# 1-Schematic_ecg_biometrics.net
KiCad netlist of a schematic drawn in EasyEDA
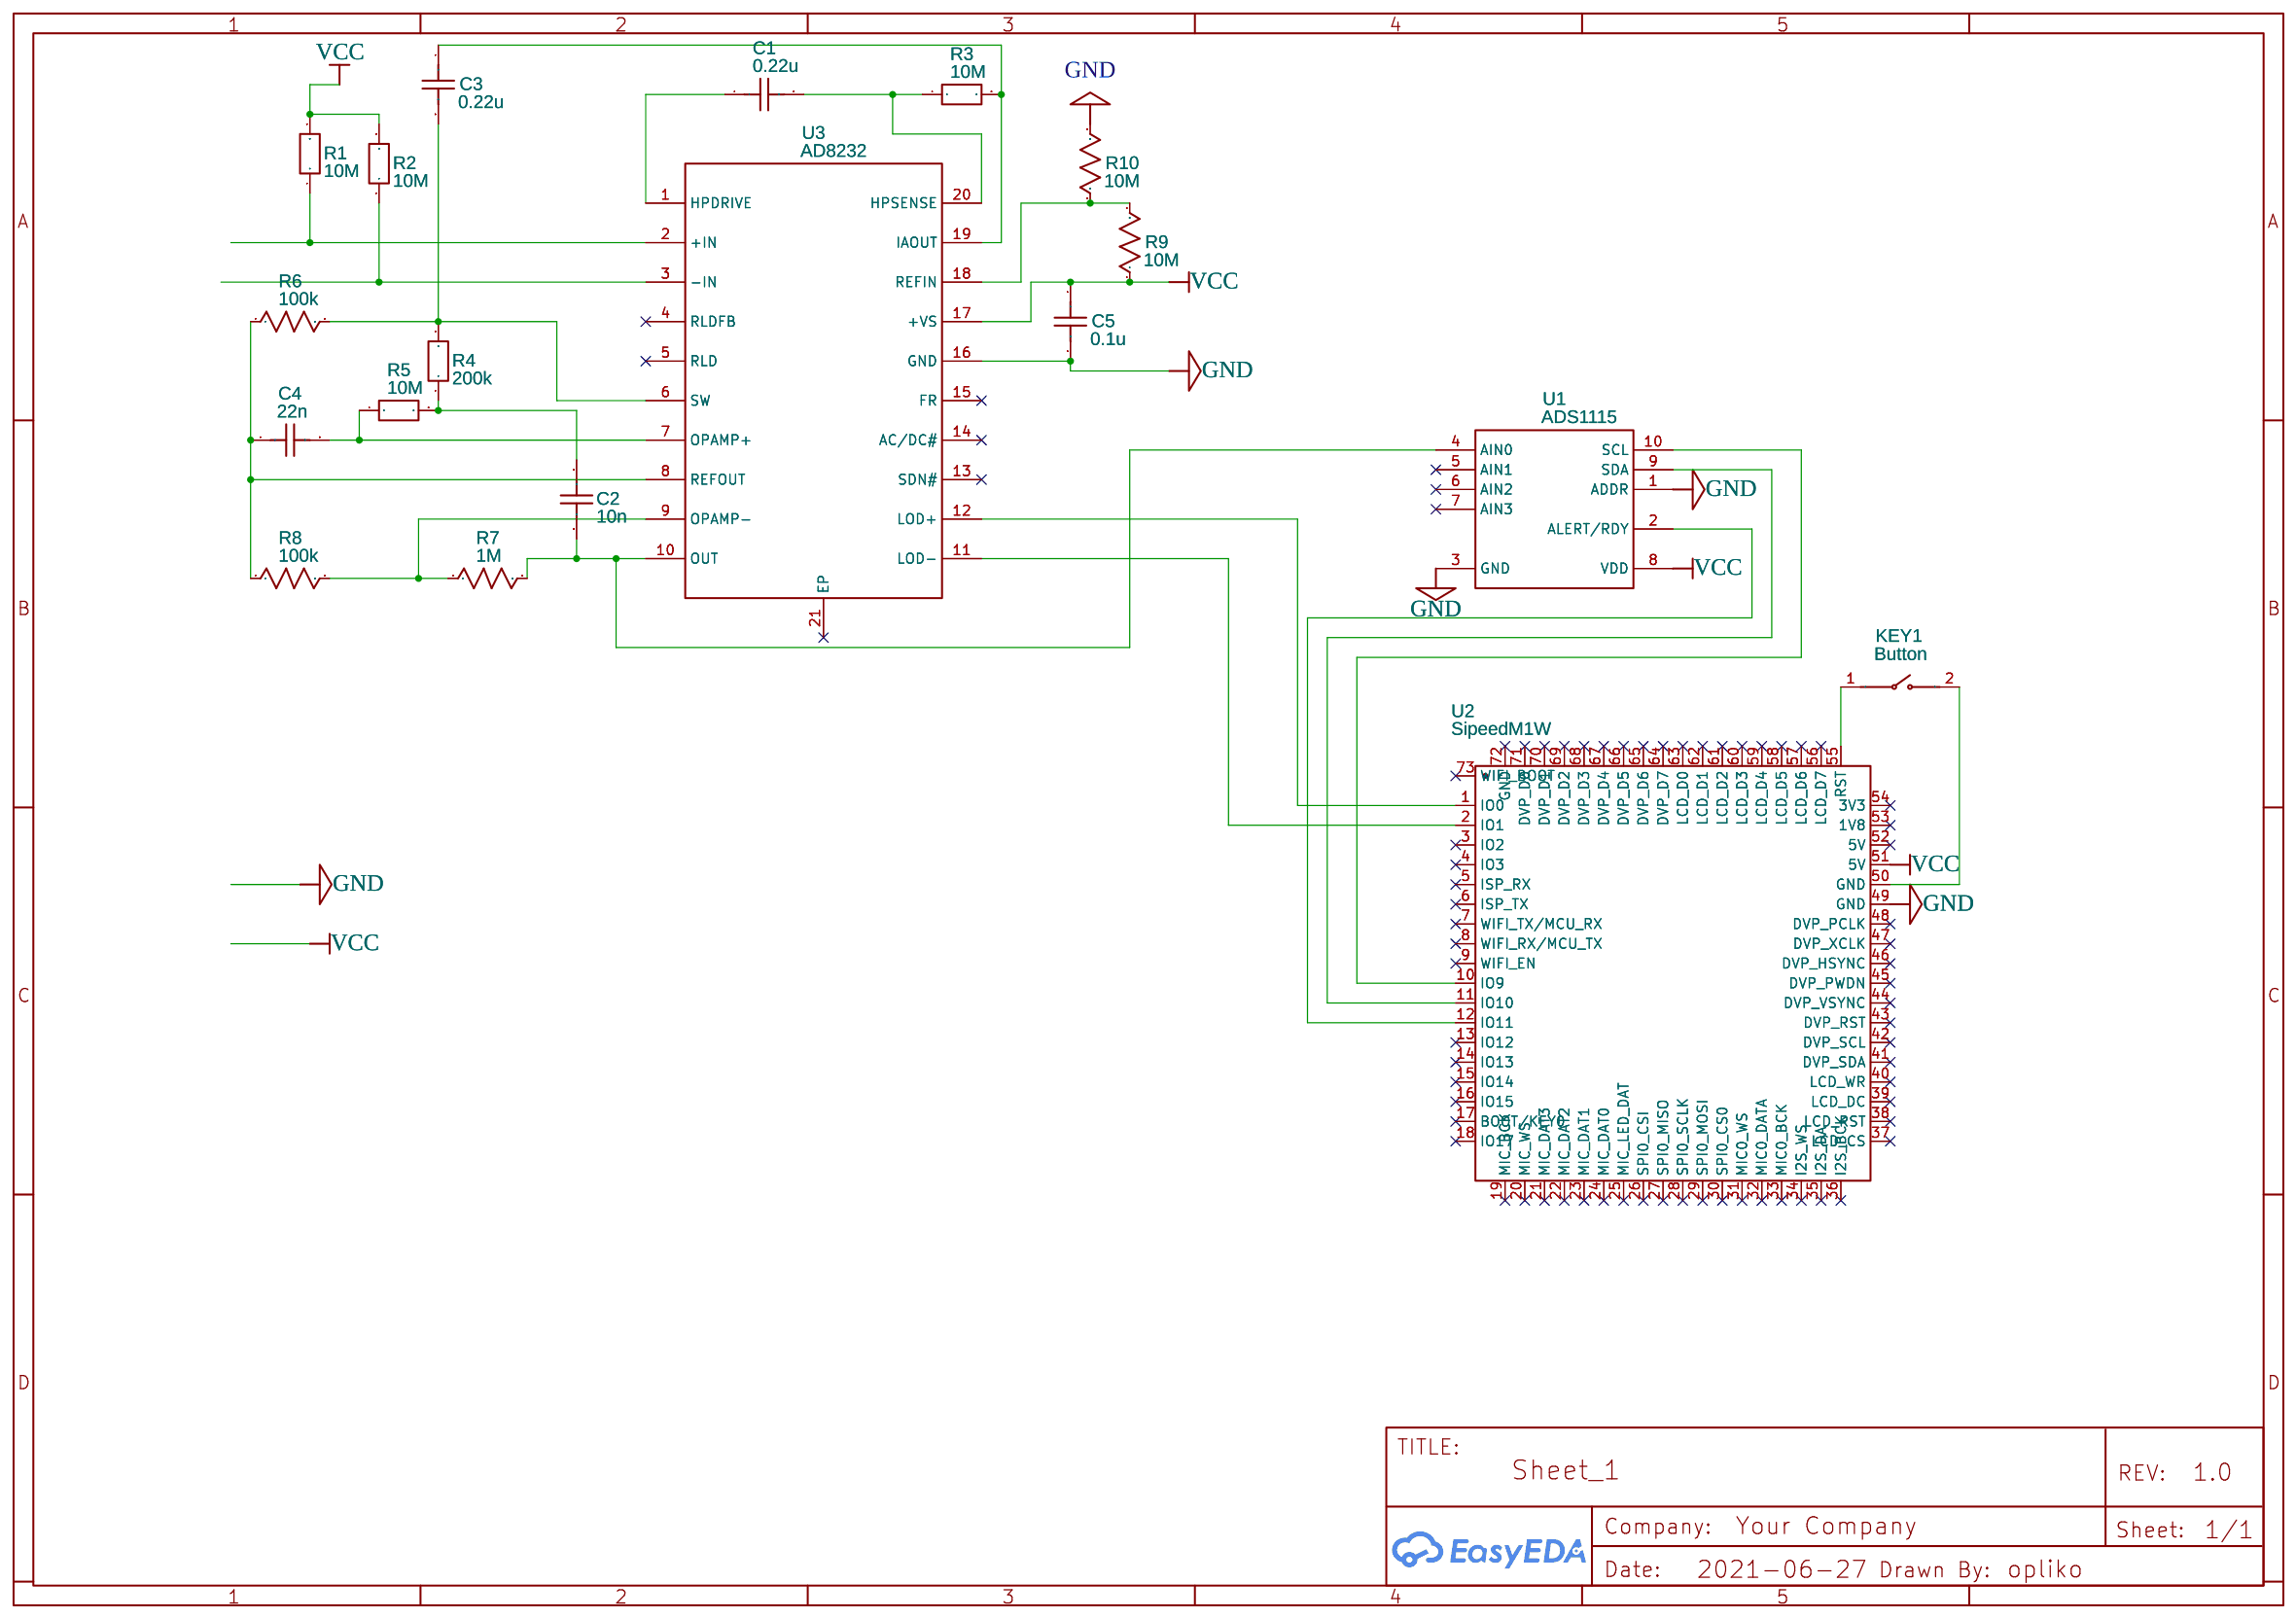
[diagram p0: schematic sheet]

(export (version "E")
  (design (tool "Eeschema 10.0.6"))
  (components
    (comp (ref "C1") (value "0.22u") (libsource (lib "") (part "C_0603_US_1")))
    (comp (ref "C2") (value "10n") (libsource (lib "") (part "C_0603_US")))
    (comp (ref "C3") (value "0.22u") (libsource (lib "") (part "C_0603_US")))
    (comp (ref "C4") (value "22n") (libsource (lib "") (part "C_0603_US_1")))
    (comp (ref "C5") (value "0.1u") (libsource (lib "") (part "C_0603_US")))
    (comp (ref "KEY1") (value "Button") (libsource (lib "") (part "Button")))
    (comp (ref "R1") (value "10M") (libsource (lib "") (part "R_0603_EU")))
    (comp (ref "R2") (value "10M") (libsource (lib "") (part "R_0603_EU")))
    (comp (ref "R3") (value "10M") (libsource (lib "") (part "R_0603_EU_1")))
    (comp (ref "R4") (value "200k") (libsource (lib "") (part "R_0603_EU")))
    (comp (ref "R5") (value "10M") (libsource (lib "") (part "R_0603_EU_1")))
    (comp (ref "R6") (value "100k") (libsource (lib "") (part "R_0603_US_1")))
    (comp (ref "R7") (value "1M") (libsource (lib "") (part "R_0603_US_1")))
    (comp (ref "R8") (value "100k") (libsource (lib "") (part "R_0603_US_1")))
    (comp (ref "R9") (value "10M") (libsource (lib "") (part "R_0603_US")))
    (comp (ref "R10") (value "10M") (libsource (lib "") (part "R_0603_US")))
    (comp (ref "U1")
      (value "ADS1115")
      (fields
        (field (name "BOM_Manufacturer Part") "ADS1115IDGSR")
        (field (name "BOM_Supplier Part") "C37593")
      )
      (libsource (lib "") (part "ADS1115"))
    )
    (comp (ref "U2")
      (value "SipeedM1W")
      (fields (field (name "BOM_Manufacturer Part") "M1W"))
      (libsource (lib "") (part "SipeedM1W"))
    )
    (comp (ref "U3")
      (value "AD8232")
      (fields
        (field (name "BOM_Manufacturer Part") "AD8232ACPZ-R7")
        (field (name "BOM_Supplier Part") "C43216")
      )
      (libsource (lib "") (part "AD8232"))
    )
  )
  (nets
    (net (code "1") (name "GND") (class "Default")
      (node (ref "C5") (pin "2") (pinfunction "2_2") (pintype "unspecified"))
      (node (ref "R10") (pin "2") (pinfunction "2_2") (pintype "unspecified"))
      (node (ref "U1") (pin "1") (pinfunction "ADDR_1") (pintype "unspecified"))
      (node (ref "U1") (pin "3") (pinfunction "GND_3") (pintype "passive"))
      (node (ref "U2") (pin "49") (pinfunction "GND_49") (pintype "unspecified"))
      (node (ref "U3") (pin "16") (pinfunction "GND_16") (pintype "unspecified"))
    )
    (net (code "2") (name "Net-(C2-Pad1)") (class "Default")
      (node (ref "C2") (pin "1") (pinfunction "1_1") (pintype "unspecified"))
      (node (ref "R4") (pin "1") (pinfunction "1_1") (pintype "unspecified"))
      (node (ref "R5") (pin "2") (pinfunction "2_2") (pintype "unspecified"))
    )
    (net (code "3") (name "Net-(KEY1-Pad2)") (class "Default")
      (node (ref "KEY1") (pin "2") (pinfunction "2_2") (pintype "unspecified"))
      (node (ref "U2") (pin "50") (pinfunction "GND_50") (pintype "unspecified"))
    )
    (net (code "4") (name "Net-(U1-AIN0)") (class "Default")
      (node (ref "C2") (pin "2") (pinfunction "2_2") (pintype "unspecified"))
      (node (ref "R7") (pin "2") (pinfunction "2_2") (pintype "unspecified"))
      (node (ref "U1") (pin "4") (pinfunction "AIN0_4") (pintype "unspecified"))
      (node (ref "U3") (pin "10") (pinfunction "OUT_10") (pintype "unspecified"))
    )
    (net (code "5") (name "Net-(U1-ALERT{slash}RDY)") (class "Default")
      (node (ref "U1") (pin "2") (pinfunction "ALERT/RDY_2") (pintype "unspecified"))
      (node (ref "U2") (pin "12") (pinfunction "IO11_12") (pintype "unspecified"))
    )
    (net (code "6") (name "Net-(U1-SCL)") (class "Default")
      (node (ref "U1") (pin "10") (pinfunction "SCL_10") (pintype "unspecified"))
      (node (ref "U2") (pin "10") (pinfunction "IO9_10") (pintype "unspecified"))
    )
    (net (code "7") (name "Net-(U1-SDA)") (class "Default")
      (node (ref "U1") (pin "9") (pinfunction "SDA_9") (pintype "bidirectional"))
      (node (ref "U2") (pin "11") (pinfunction "IO10_11") (pintype "unspecified"))
    )
    (net (code "8") (name "Net-(U2-IO0)") (class "Default")
      (node (ref "U2") (pin "1") (pinfunction "IO0_1") (pintype "unspecified"))
      (node (ref "U3") (pin "12") (pinfunction "LOD+_12") (pintype "unspecified"))
    )
    (net (code "9") (name "Net-(U2-IO1)") (class "Default")
      (node (ref "U2") (pin "2") (pinfunction "IO1_2") (pintype "unspecified"))
      (node (ref "U3") (pin "11") (pinfunction "LOD-_11") (pintype "unspecified"))
    )
    (net (code "10") (name "Net-(U2-RST)") (class "Default")
      (node (ref "KEY1") (pin "1") (pinfunction "1_1") (pintype "unspecified"))
      (node (ref "U2") (pin "55") (pinfunction "RST_55") (pintype "unspecified"))
    )
    (net (code "11") (name "Net-(U3-+IN)") (class "Default")
      (node (ref "R1") (pin "1") (pinfunction "1_1") (pintype "unspecified"))
      (node (ref "U3") (pin "2") (pinfunction "+IN_2") (pintype "unspecified"))
    )
    (net (code "12") (name "Net-(U3--IN)") (class "Default")
      (node (ref "R2") (pin "1") (pinfunction "1_1") (pintype "unspecified"))
      (node (ref "U3") (pin "3") (pinfunction "-IN_3") (pintype "unspecified"))
    )
    (net (code "13") (name "Net-(U3-HPDRIVE)") (class "Default")
      (node (ref "C1") (pin "1") (pinfunction "1_1") (pintype "unspecified"))
      (node (ref "U3") (pin "1") (pinfunction "HPDRIVE_1") (pintype "unspecified"))
    )
    (net (code "14") (name "Net-(U3-HPSENSE)") (class "Default")
      (node (ref "C1") (pin "2") (pinfunction "2_2") (pintype "unspecified"))
      (node (ref "R3") (pin "1") (pinfunction "1_1") (pintype "unspecified"))
      (node (ref "U3") (pin "20") (pinfunction "HPSENSE_20") (pintype "unspecified"))
    )
    (net (code "15") (name "Net-(U3-IAOUT)") (class "Default")
      (node (ref "C3") (pin "1") (pinfunction "1_1") (pintype "unspecified"))
      (node (ref "R3") (pin "2") (pinfunction "2_2") (pintype "unspecified"))
      (node (ref "U3") (pin "19") (pinfunction "IAOUT_19") (pintype "unspecified"))
    )
    (net (code "16") (name "Net-(U3-OPAMP+)") (class "Default")
      (node (ref "C4") (pin "2") (pinfunction "2_2") (pintype "unspecified"))
      (node (ref "R5") (pin "1") (pinfunction "1_1") (pintype "unspecified"))
      (node (ref "U3") (pin "7") (pinfunction "OPAMP+_7") (pintype "unspecified"))
    )
    (net (code "17") (name "Net-(U3-OPAMP-)") (class "Default")
      (node (ref "R7") (pin "1") (pinfunction "1_1") (pintype "unspecified"))
      (node (ref "R8") (pin "2") (pinfunction "2_2") (pintype "unspecified"))
      (node (ref "U3") (pin "9") (pinfunction "OPAMP-_9") (pintype "unspecified"))
    )
    (net (code "18") (name "Net-(U3-REFIN)") (class "Default")
      (node (ref "R10") (pin "1") (pinfunction "1_1") (pintype "unspecified"))
      (node (ref "R9") (pin "2") (pinfunction "2_2") (pintype "unspecified"))
      (node (ref "U3") (pin "18") (pinfunction "REFIN_18") (pintype "unspecified"))
    )
    (net (code "19") (name "Net-(U3-REFOUT)") (class "Default")
      (node (ref "C4") (pin "1") (pinfunction "1_1") (pintype "unspecified"))
      (node (ref "R6") (pin "1") (pinfunction "1_1") (pintype "unspecified"))
      (node (ref "R8") (pin "1") (pinfunction "1_1") (pintype "unspecified"))
      (node (ref "U3") (pin "8") (pinfunction "REFOUT_8") (pintype "unspecified"))
    )
    (net (code "20") (name "Net-(U3-SW)") (class "Default")
      (node (ref "C3") (pin "2") (pinfunction "2_2") (pintype "unspecified"))
      (node (ref "R4") (pin "2") (pinfunction "2_2") (pintype "unspecified"))
      (node (ref "R6") (pin "2") (pinfunction "2_2") (pintype "unspecified"))
      (node (ref "U3") (pin "6") (pinfunction "SW_6") (pintype "unspecified"))
    )
    (net (code "21") (name "VCC") (class "Default")
      (node (ref "C5") (pin "1") (pinfunction "1_1") (pintype "unspecified"))
      (node (ref "R1") (pin "2") (pinfunction "2_2") (pintype "unspecified"))
      (node (ref "R2") (pin "2") (pinfunction "2_2") (pintype "unspecified"))
      (node (ref "R9") (pin "1") (pinfunction "1_1") (pintype "unspecified"))
      (node (ref "U1") (pin "8") (pinfunction "VDD_8") (pintype "passive"))
      (node (ref "U2") (pin "51") (pinfunction "5V_51") (pintype "unspecified"))
      (node (ref "U3") (pin "17") (pinfunction "+VS_17") (pintype "unspecified"))
    )
    (net (code "22") (name "unconnected-(U1-AIN1-Pad5)") (class "Default")
      (node (ref "U1") (pin "5") (pinfunction "AIN1_5") (pintype "unspecified+no_connect"))
    )
    (net (code "23") (name "unconnected-(U1-AIN2-Pad6)") (class "Default")
      (node (ref "U1") (pin "6") (pinfunction "AIN2_6") (pintype "unspecified+no_connect"))
    )
    (net (code "24") (name "unconnected-(U1-AIN3-Pad7)") (class "Default")
      (node (ref "U1") (pin "7") (pinfunction "AIN3_7") (pintype "unspecified+no_connect"))
    )
    (net (code "25") (name "unconnected-(U2-1V8-Pad53)") (class "Default")
      (node (ref "U2") (pin "53") (pinfunction "1V8_53") (pintype "unspecified+no_connect"))
    )
    (net (code "26") (name "unconnected-(U2-3V3-Pad54)") (class "Default")
      (node (ref "U2") (pin "54") (pinfunction "3V3_54") (pintype "unspecified+no_connect"))
    )
    (net (code "27") (name "unconnected-(U2-5V-Pad52)") (class "Default")
      (node (ref "U2") (pin "52") (pinfunction "5V_52") (pintype "unspecified+no_connect"))
    )
    (net (code "28") (name "unconnected-(U2-BOOT{slash}KEY0-Pad17)") (class "Default")
      (node (ref "U2") (pin "17") (pinfunction "BOOT/KEY0_17") (pintype "unspecified+no_connect"))
    )
    (net (code "29") (name "unconnected-(U2-DVP_D0-Pad71)") (class "Default")
      (node (ref "U2") (pin "71") (pinfunction "DVP_D0_71") (pintype "unspecified+no_connect"))
    )
    (net (code "30") (name "unconnected-(U2-DVP_D1-Pad70)") (class "Default")
      (node (ref "U2") (pin "70") (pinfunction "DVP_D1_70") (pintype "unspecified+no_connect"))
    )
    (net (code "31") (name "unconnected-(U2-DVP_D2-Pad69)") (class "Default")
      (node (ref "U2") (pin "69") (pinfunction "DVP_D2_69") (pintype "unspecified+no_connect"))
    )
    (net (code "32") (name "unconnected-(U2-DVP_D3-Pad68)") (class "Default")
      (node (ref "U2") (pin "68") (pinfunction "DVP_D3_68") (pintype "unspecified+no_connect"))
    )
    (net (code "33") (name "unconnected-(U2-DVP_D4-Pad67)") (class "Default")
      (node (ref "U2") (pin "67") (pinfunction "DVP_D4_67") (pintype "unspecified+no_connect"))
    )
    (net (code "34") (name "unconnected-(U2-DVP_D5-Pad66)") (class "Default")
      (node (ref "U2") (pin "66") (pinfunction "DVP_D5_66") (pintype "unspecified+no_connect"))
    )
    (net (code "35") (name "unconnected-(U2-DVP_D6-Pad65)") (class "Default")
      (node (ref "U2") (pin "65") (pinfunction "DVP_D6_65") (pintype "unspecified+no_connect"))
    )
    (net (code "36") (name "unconnected-(U2-DVP_D7-Pad64)") (class "Default")
      (node (ref "U2") (pin "64") (pinfunction "DVP_D7_64") (pintype "unspecified+no_connect"))
    )
    (net (code "37") (name "unconnected-(U2-DVP_HSYNC-Pad46)") (class "Default")
      (node (ref "U2") (pin "46") (pinfunction "DVP_HSYNC_46") (pintype "unspecified+no_connect"))
    )
    (net (code "38") (name "unconnected-(U2-DVP_PCLK-Pad48)") (class "Default")
      (node (ref "U2") (pin "48") (pinfunction "DVP_PCLK_48") (pintype "unspecified+no_connect"))
    )
    (net (code "39") (name "unconnected-(U2-DVP_PWDN-Pad45)") (class "Default")
      (node (ref "U2") (pin "45") (pinfunction "DVP_PWDN_45") (pintype "unspecified+no_connect"))
    )
    (net (code "40") (name "unconnected-(U2-DVP_RST-Pad43)") (class "Default")
      (node (ref "U2") (pin "43") (pinfunction "DVP_RST_43") (pintype "unspecified+no_connect"))
    )
    (net (code "41") (name "unconnected-(U2-DVP_SCL-Pad42)") (class "Default")
      (node (ref "U2") (pin "42") (pinfunction "DVP_SCL_42") (pintype "unspecified+no_connect"))
    )
    (net (code "42") (name "unconnected-(U2-DVP_SDA-Pad41)") (class "Default")
      (node (ref "U2") (pin "41") (pinfunction "DVP_SDA_41") (pintype "unspecified+no_connect"))
    )
    (net (code "43") (name "unconnected-(U2-DVP_VSYNC-Pad44)") (class "Default")
      (node (ref "U2") (pin "44") (pinfunction "DVP_VSYNC_44") (pintype "unspecified+no_connect"))
    )
    (net (code "44") (name "unconnected-(U2-DVP_XCLK-Pad47)") (class "Default")
      (node (ref "U2") (pin "47") (pinfunction "DVP_XCLK_47") (pintype "unspecified+no_connect"))
    )
    (net (code "45") (name "unconnected-(U2-GND-Pad72)") (class "Default")
      (node (ref "U2") (pin "72") (pinfunction "GND_72") (pintype "unspecified+no_connect"))
    )
    (net (code "46") (name "unconnected-(U2-I2S_BCK-Pad36)") (class "Default")
      (node (ref "U2") (pin "36") (pinfunction "I2S_BCK_36") (pintype "unspecified+no_connect"))
    )
    (net (code "47") (name "unconnected-(U2-I2S_DA-Pad35)") (class "Default")
      (node (ref "U2") (pin "35") (pinfunction "I2S_DA_35") (pintype "unspecified+no_connect"))
    )
    (net (code "48") (name "unconnected-(U2-I2S_WS-Pad34)") (class "Default")
      (node (ref "U2") (pin "34") (pinfunction "I2S_WS_34") (pintype "unspecified+no_connect"))
    )
    (net (code "49") (name "unconnected-(U2-IO2-Pad3)") (class "Default")
      (node (ref "U2") (pin "3") (pinfunction "IO2_3") (pintype "unspecified+no_connect"))
    )
    (net (code "50") (name "unconnected-(U2-IO3-Pad4)") (class "Default")
      (node (ref "U2") (pin "4") (pinfunction "IO3_4") (pintype "unspecified+no_connect"))
    )
    (net (code "51") (name "unconnected-(U2-IO12-Pad13)") (class "Default")
      (node (ref "U2") (pin "13") (pinfunction "IO12_13") (pintype "unspecified+no_connect"))
    )
    (net (code "52") (name "unconnected-(U2-IO13-Pad14)") (class "Default")
      (node (ref "U2") (pin "14") (pinfunction "IO13_14") (pintype "unspecified+no_connect"))
    )
    (net (code "53") (name "unconnected-(U2-IO14-Pad15)") (class "Default")
      (node (ref "U2") (pin "15") (pinfunction "IO14_15") (pintype "unspecified+no_connect"))
    )
    (net (code "54") (name "unconnected-(U2-IO15-Pad16)") (class "Default")
      (node (ref "U2") (pin "16") (pinfunction "IO15_16") (pintype "unspecified+no_connect"))
    )
    (net (code "55") (name "unconnected-(U2-IO17-Pad18)") (class "Default")
      (node (ref "U2") (pin "18") (pinfunction "IO17_18") (pintype "unspecified+no_connect"))
    )
    (net (code "56") (name "unconnected-(U2-ISP_RX-Pad5)") (class "Default")
      (node (ref "U2") (pin "5") (pinfunction "ISP_RX_5") (pintype "unspecified+no_connect"))
    )
    (net (code "57") (name "unconnected-(U2-ISP_TX-Pad6)") (class "Default")
      (node (ref "U2") (pin "6") (pinfunction "ISP_TX_6") (pintype "unspecified+no_connect"))
    )
    (net (code "58") (name "unconnected-(U2-LCD_CS-Pad37)") (class "Default")
      (node (ref "U2") (pin "37") (pinfunction "LCD_CS_37") (pintype "unspecified+no_connect"))
    )
    (net (code "59") (name "unconnected-(U2-LCD_D0-Pad63)") (class "Default")
      (node (ref "U2") (pin "63") (pinfunction "LCD_D0_63") (pintype "unspecified+no_connect"))
    )
    (net (code "60") (name "unconnected-(U2-LCD_D1-Pad62)") (class "Default")
      (node (ref "U2") (pin "62") (pinfunction "LCD_D1_62") (pintype "unspecified+no_connect"))
    )
    (net (code "61") (name "unconnected-(U2-LCD_D2-Pad61)") (class "Default")
      (node (ref "U2") (pin "61") (pinfunction "LCD_D2_61") (pintype "unspecified+no_connect"))
    )
    (net (code "62") (name "unconnected-(U2-LCD_D3-Pad60)") (class "Default")
      (node (ref "U2") (pin "60") (pinfunction "LCD_D3_60") (pintype "unspecified+no_connect"))
    )
    (net (code "63") (name "unconnected-(U2-LCD_D4-Pad59)") (class "Default")
      (node (ref "U2") (pin "59") (pinfunction "LCD_D4_59") (pintype "unspecified+no_connect"))
    )
    (net (code "64") (name "unconnected-(U2-LCD_D5-Pad58)") (class "Default")
      (node (ref "U2") (pin "58") (pinfunction "LCD_D5_58") (pintype "unspecified+no_connect"))
    )
    (net (code "65") (name "unconnected-(U2-LCD_D6-Pad57)") (class "Default")
      (node (ref "U2") (pin "57") (pinfunction "LCD_D6_57") (pintype "unspecified+no_connect"))
    )
    (net (code "66") (name "unconnected-(U2-LCD_D7-Pad56)") (class "Default")
      (node (ref "U2") (pin "56") (pinfunction "LCD_D7_56") (pintype "unspecified+no_connect"))
    )
    (net (code "67") (name "unconnected-(U2-LCD_DC-Pad39)") (class "Default")
      (node (ref "U2") (pin "39") (pinfunction "LCD_DC_39") (pintype "unspecified+no_connect"))
    )
    (net (code "68") (name "unconnected-(U2-LCD_RST-Pad38)") (class "Default")
      (node (ref "U2") (pin "38") (pinfunction "LCD_RST_38") (pintype "unspecified+no_connect"))
    )
    (net (code "69") (name "unconnected-(U2-LCD_WR-Pad40)") (class "Default")
      (node (ref "U2") (pin "40") (pinfunction "LCD_WR_40") (pintype "unspecified+no_connect"))
    )
    (net (code "70") (name "unconnected-(U2-MIC0_BCK-Pad33)") (class "Default")
      (node (ref "U2") (pin "33") (pinfunction "MIC0_BCK_33") (pintype "unspecified+no_connect"))
    )
    (net (code "71") (name "unconnected-(U2-MIC0_DATA-Pad32)") (class "Default")
      (node (ref "U2") (pin "32") (pinfunction "MIC0_DATA_32") (pintype "unspecified+no_connect"))
    )
    (net (code "72") (name "unconnected-(U2-MIC0_WS-Pad31)") (class "Default")
      (node (ref "U2") (pin "31") (pinfunction "MIC0_WS_31") (pintype "unspecified+no_connect"))
    )
    (net (code "73") (name "unconnected-(U2-MIC_BCK-Pad19)") (class "Default")
      (node (ref "U2") (pin "19") (pinfunction "MIC_BCK_19") (pintype "unspecified+no_connect"))
    )
    (net (code "74") (name "unconnected-(U2-MIC_DAT0-Pad24)") (class "Default")
      (node (ref "U2") (pin "24") (pinfunction "MIC_DAT0_24") (pintype "unspecified+no_connect"))
    )
    (net (code "75") (name "unconnected-(U2-MIC_DAT1-Pad23)") (class "Default")
      (node (ref "U2") (pin "23") (pinfunction "MIC_DAT1_23") (pintype "unspecified+no_connect"))
    )
    (net (code "76") (name "unconnected-(U2-MIC_DAT2-Pad22)") (class "Default")
      (node (ref "U2") (pin "22") (pinfunction "MIC_DAT2_22") (pintype "unspecified+no_connect"))
    )
    (net (code "77") (name "unconnected-(U2-MIC_DAT3-Pad21)") (class "Default")
      (node (ref "U2") (pin "21") (pinfunction "MIC_DAT3_21") (pintype "unspecified+no_connect"))
    )
    (net (code "78") (name "unconnected-(U2-MIC_LED_DAT-Pad25)") (class "Default")
      (node (ref "U2") (pin "25") (pinfunction "MIC_LED_DAT_25") (pintype "unspecified+no_connect"))
    )
    (net (code "79") (name "unconnected-(U2-MIC_WS-Pad20)") (class "Default")
      (node (ref "U2") (pin "20") (pinfunction "MIC_WS_20") (pintype "unspecified+no_connect"))
    )
    (net (code "80") (name "unconnected-(U2-SPI0_CS0-Pad30)") (class "Default")
      (node (ref "U2") (pin "30") (pinfunction "SPI0_CS0_30") (pintype "unspecified+no_connect"))
    )
    (net (code "81") (name "unconnected-(U2-SPI0_CSI-Pad26)") (class "Default")
      (node (ref "U2") (pin "26") (pinfunction "SPI0_CSI_26") (pintype "unspecified+no_connect"))
    )
    (net (code "82") (name "unconnected-(U2-SPI0_MISO-Pad27)") (class "Default")
      (node (ref "U2") (pin "27") (pinfunction "SPI0_MISO_27") (pintype "unspecified+no_connect"))
    )
    (net (code "83") (name "unconnected-(U2-SPI0_MOSI-Pad29)") (class "Default")
      (node (ref "U2") (pin "29") (pinfunction "SPI0_MOSI_29") (pintype "unspecified+no_connect"))
    )
    (net (code "84") (name "unconnected-(U2-SPI0_SCLK-Pad28)") (class "Default")
      (node (ref "U2") (pin "28") (pinfunction "SPI0_SCLK_28") (pintype "unspecified+no_connect"))
    )
    (net (code "85") (name "unconnected-(U2-WIFI_BOOT-Pad73)") (class "Default")
      (node (ref "U2") (pin "73") (pinfunction "WIFI_BOOT_73") (pintype "unspecified+no_connect"))
    )
    (net (code "86") (name "unconnected-(U2-WIFI_EN-Pad9)") (class "Default")
      (node (ref "U2") (pin "9") (pinfunction "WIFI_EN_9") (pintype "unspecified+no_connect"))
    )
    (net (code "87") (name "unconnected-(U2-WIFI_RX{slash}MCU_TX-Pad8)") (class "Default")
      (node (ref "U2") (pin "8") (pinfunction "WIFI_RX/MCU_TX_8") (pintype "unspecified+no_connect"))
    )
    (net (code "88") (name "unconnected-(U2-WIFI_TX{slash}MCU_RX-Pad7)") (class "Default")
      (node (ref "U2") (pin "7") (pinfunction "WIFI_TX/MCU_RX_7") (pintype "unspecified+no_connect"))
    )
    (net (code "89") (name "unconnected-(U3-AC{slash}DC#-Pad14)") (class "Default")
      (node (ref "U3") (pin "14") (pinfunction "AC/DC#_14") (pintype "unspecified+no_connect"))
    )
    (net (code "90") (name "unconnected-(U3-EP-Pad21)") (class "Default")
      (node (ref "U3") (pin "21") (pinfunction "EP_21") (pintype "unspecified+no_connect"))
    )
    (net (code "91") (name "unconnected-(U3-FR-Pad15)") (class "Default")
      (node (ref "U3") (pin "15") (pinfunction "FR_15") (pintype "unspecified+no_connect"))
    )
    (net (code "92") (name "unconnected-(U3-RLD-Pad5)") (class "Default")
      (node (ref "U3") (pin "5") (pinfunction "RLD_5") (pintype "unspecified+no_connect"))
    )
    (net (code "93") (name "unconnected-(U3-RLDFB-Pad4)") (class "Default")
      (node (ref "U3") (pin "4") (pinfunction "RLDFB_4") (pintype "unspecified+no_connect"))
    )
    (net (code "94") (name "unconnected-(U3-SDN#-Pad13)") (class "Default")
      (node (ref "U3") (pin "13") (pinfunction "SDN#_13") (pintype "unspecified+no_connect"))
    )
  )
)
